# ClockGenerator.net
KiCad netlist of a schematic drawn in Altium Designer
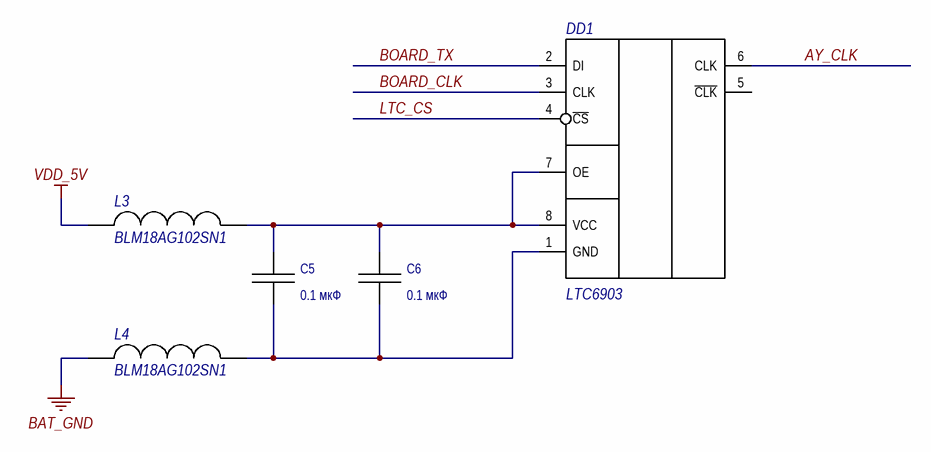
[diagram p0: ClockGenerator.SchDoc]

(export (version "E")
  (design (tool "Eeschema 10.0.6"))
  (components
    (comp (ref "C5")
      (value "0.1 мкФ")
      (footprint "C 1206")
      (description "SMD Capacitor 1206")
      (fields
        (field (name "TOLERANCE") "/Укажите допуск в процентах/")
        (field (name "MANUFACTURER") "/Укажите компанию-производителя/")
      )
      (libsource (lib "my_lib") (part "CAP 1206"))
    )
    (comp (ref "C6")
      (value "0.1 мкФ")
      (footprint "C 1206")
      (description "SMD Capacitor 1206")
      (fields
        (field (name "TOLERANCE") "/Укажите допуск в процентах/")
        (field (name "MANUFACTURER") "/Укажите компанию-производителя/")
      )
      (libsource (lib "my_lib") (part "CAP 1206"))
    )
    (comp (ref "DD1") (value "LTC6903") (footprint "MSOP_MS8") (libsource (lib "my_lib") (part "LTC6903")))
    (comp (ref "L3")
      (value "BLM18AG102SN1")
      (footprint "FB 0603")
      (libsource (lib "my_lib") (part "BLM18AG102SN1"))
    )
    (comp (ref "L4")
      (value "BLM18AG102SN1")
      (footprint "FB 0603")
      (libsource (lib "my_lib") (part "BLM18AG102SN1"))
    )
  )
  (nets
    (net (code "1") (name "/AY_CLK") (class "Default")
      (node (ref "DD1") (pin "6") (pinfunction "CLK_6") (pintype "passive"))
    )
    (net (code "2") (name "/BOARD_CLK") (class "Default")
      (node (ref "DD1") (pin "3") (pinfunction "CLK_3") (pintype "passive"))
    )
    (net (code "3") (name "/BOARD_TX") (class "Default")
      (node (ref "DD1") (pin "2") (pinfunction "DI_2") (pintype "passive"))
    )
    (net (code "4") (name "/LTC_CS") (class "Default")
      (node (ref "DD1") (pin "4") (pinfunction "~{CS}_4") (pintype "passive"))
    )
    (net (code "5") (name "BAT_GND") (class "Default")
      (node (ref "L4") (pin "1") (pinfunction "1_1") (pintype "passive"))
    )
    (net (code "6") (name "Net-(DD1-GND)") (class "Default")
      (node (ref "C5") (pin "2") (pinfunction "2_2") (pintype "passive"))
      (node (ref "C6") (pin "2") (pinfunction "2_2") (pintype "passive"))
      (node (ref "DD1") (pin "1") (pinfunction "GND_1") (pintype "passive"))
      (node (ref "L4") (pin "2") (pinfunction "2_2") (pintype "passive"))
    )
    (net (code "7") (name "Net-(DD1-OE)") (class "Default")
      (node (ref "C5") (pin "1") (pinfunction "1_1") (pintype "passive"))
      (node (ref "C6") (pin "1") (pinfunction "1_1") (pintype "passive"))
      (node (ref "DD1") (pin "7") (pinfunction "OE_7") (pintype "passive"))
      (node (ref "DD1") (pin "8") (pinfunction "VCC_8") (pintype "passive"))
      (node (ref "L3") (pin "2") (pinfunction "2_2") (pintype "passive"))
    )
    (net (code "8") (name "VDD_5V") (class "Default")
      (node (ref "L3") (pin "1") (pinfunction "1_1") (pintype "passive"))
    )
    (net (code "9") (name "unconnected-(DD1-~{CLK}-Pad5)") (class "Default")
      (node (ref "DD1") (pin "5") (pinfunction "~{CLK}_5") (pintype "passive"))
    )
  )
)
